# SparkFun_Blackberry_Trackballer_Breakout.net
KiCad netlist of a schematic drawn in EAGLE
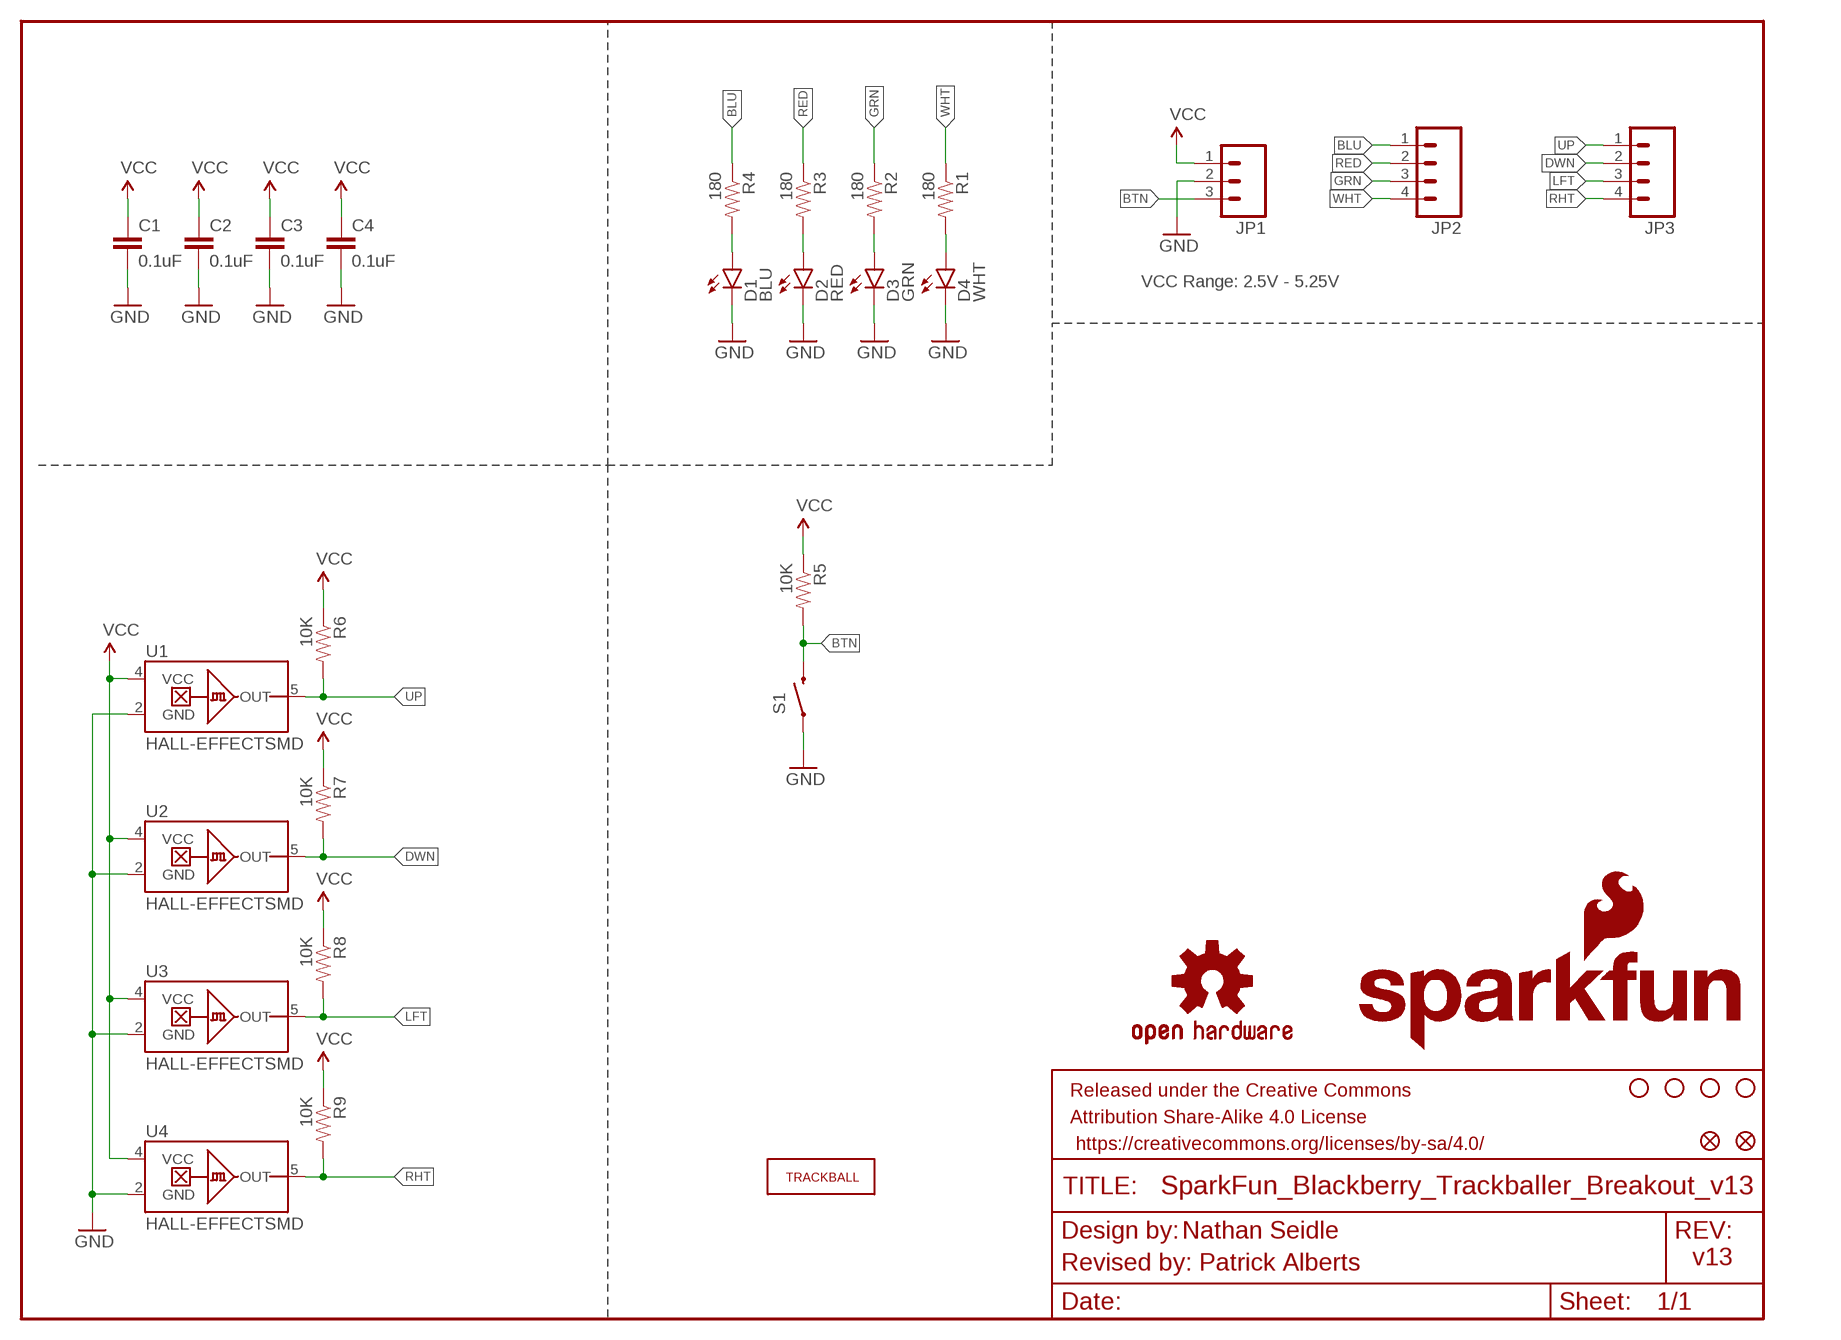
[diagram p0: schematic, sheet 1]

(export (version "E")
  (design (tool "Eeschema 10.0.6"))
  (components
    (comp (ref "C1")
      (value "0.1uF")
      (footprint "eagle-import:0603-CAP")
      (libsource (lib "eagle-import") (part "0.1UF-25V(+80/-20%)(0603)"))
    )
    (comp (ref "C2")
      (value "0.1uF")
      (footprint "eagle-import:0603-CAP")
      (libsource (lib "eagle-import") (part "0.1UF-25V(+80/-20%)(0603)"))
    )
    (comp (ref "C3")
      (value "0.1uF")
      (footprint "eagle-import:0603-CAP")
      (libsource (lib "eagle-import") (part "0.1UF-25V(+80/-20%)(0603)"))
    )
    (comp (ref "C4")
      (value "0.1uF")
      (footprint "eagle-import:0603-CAP")
      (libsource (lib "eagle-import") (part "0.1UF-25V(+80/-20%)(0603)"))
    )
    (comp (ref "D1")
      (value "BLU")
      (footprint "eagle-import:LED-0603")
      (libsource (lib "eagle-import") (part "LED-BLUE0603"))
    )
    (comp (ref "D2")
      (value "RED")
      (footprint "eagle-import:LED-0603")
      (libsource (lib "eagle-import") (part "LED-RED0603"))
    )
    (comp (ref "D3")
      (value "GRN")
      (footprint "eagle-import:LED-0603")
      (libsource (lib "eagle-import") (part "LED-GREEN0603"))
    )
    (comp (ref "D4")
      (value "WHT")
      (footprint "eagle-import:LED-0603")
      (libsource (lib "eagle-import") (part "LED-WHITE0603"))
    )
    (comp (ref "E$1")
      (value "FIDUCIAL1X2")
      (footprint "eagle-import:FIDUCIAL-1X2")
      (libsource (lib "eagle-import") (part "FIDUCIAL1X2"))
    )
    (comp (ref "E$2")
      (value "FIDUCIAL1X2")
      (footprint "eagle-import:FIDUCIAL-1X2")
      (libsource (lib "eagle-import") (part "FIDUCIAL1X2"))
    )
    (comp (ref "FRAME1")
      (value "FRAME-LETTER")
      (footprint "eagle-import:CREATIVE_COMMONS")
      (libsource (lib "eagle-import") (part "FRAME-LETTER"))
    )
    (comp (ref "JP1")
      (value "M03PTH")
      (footprint "eagle-import:1X03")
      (libsource (lib "eagle-import") (part "M03PTH"))
    )
    (comp (ref "JP2")
      (value "M04PTH")
      (footprint "eagle-import:1X04")
      (libsource (lib "eagle-import") (part "M04PTH"))
    )
    (comp (ref "JP3")
      (value "M04PTH")
      (footprint "eagle-import:1X04")
      (libsource (lib "eagle-import") (part "M04PTH"))
    )
    (comp (ref "LOGO1")
      (value "SFE_LOGO_NAME_FLAME.2_INCH")
      (footprint "eagle-import:SFE_LOGO_NAME_FLAME_.2")
      (libsource (lib "eagle-import") (part "SFE_LOGO_NAME_FLAME.2_INCH"))
    )
    (comp (ref "LOGO2")
      (value "OSHW-LOGOS")
      (footprint "eagle-import:OSHW-LOGO-S")
      (libsource (lib "eagle-import") (part "OSHW-LOGOS"))
    )
    (comp (ref "R1")
      (value "180")
      (footprint "eagle-import:0603-RES")
      (libsource (lib "eagle-import") (part "180OHM1/10W1%(0603)"))
    )
    (comp (ref "R2")
      (value "180")
      (footprint "eagle-import:0603-RES")
      (libsource (lib "eagle-import") (part "180OHM1/10W1%(0603)"))
    )
    (comp (ref "R3")
      (value "180")
      (footprint "eagle-import:0603-RES")
      (libsource (lib "eagle-import") (part "180OHM1/10W1%(0603)"))
    )
    (comp (ref "R4")
      (value "180")
      (footprint "eagle-import:0603-RES")
      (libsource (lib "eagle-import") (part "180OHM1/10W1%(0603)"))
    )
    (comp (ref "R5")
      (value "10K")
      (footprint "eagle-import:0603-RES")
      (libsource (lib "eagle-import") (part "10KOHM1/10W1%(0603)0603"))
    )
    (comp (ref "R6")
      (value "10K")
      (footprint "eagle-import:0603-RES")
      (libsource (lib "eagle-import") (part "10KOHM1/10W1%(0603)0603"))
    )
    (comp (ref "R7")
      (value "10K")
      (footprint "eagle-import:0603-RES")
      (libsource (lib "eagle-import") (part "10KOHM1/10W1%(0603)0603"))
    )
    (comp (ref "R8")
      (value "10K")
      (footprint "eagle-import:0603-RES")
      (libsource (lib "eagle-import") (part "10KOHM1/10W1%(0603)0603"))
    )
    (comp (ref "R9")
      (value "10K")
      (footprint "eagle-import:0603-RES")
      (libsource (lib "eagle-import") (part "10KOHM1/10W1%(0603)0603"))
    )
    (comp (ref "S1")
      (value "SWITCH-MOMENTARY-2SMD-2")
      (footprint "eagle-import:TACTILE_SWITCH_SMD-2")
      (libsource (lib "eagle-import") (part "SWITCH-MOMENTARY-2SMD-2"))
    )
    (comp (ref "U$1")
      (value "STAND-OFF")
      (footprint "eagle-import:STAND-OFF")
      (libsource (lib "eagle-import") (part "STAND-OFF"))
    )
    (comp (ref "U$3")
      (value "TRACKBALLMECH")
      (footprint "eagle-import:TRACKBALL")
      (libsource (lib "eagle-import") (part "TRACKBALLMECH"))
    )
    (comp (ref "U$8")
      (value "STAND-OFF")
      (footprint "eagle-import:STAND-OFF")
      (libsource (lib "eagle-import") (part "STAND-OFF"))
    )
    (comp (ref "U$11")
      (value "STAND-OFF")
      (footprint "eagle-import:STAND-OFF")
      (libsource (lib "eagle-import") (part "STAND-OFF"))
    )
    (comp (ref "U$14")
      (value "STAND-OFF")
      (footprint "eagle-import:STAND-OFF")
      (libsource (lib "eagle-import") (part "STAND-OFF"))
    )
    (comp (ref "U1")
      (value "HALL-EFFECTSMD")
      (footprint "eagle-import:SC70")
      (libsource (lib "eagle-import") (part "HALL-EFFECTSMD"))
    )
    (comp (ref "U2")
      (value "HALL-EFFECTSMD")
      (footprint "eagle-import:SC70")
      (libsource (lib "eagle-import") (part "HALL-EFFECTSMD"))
    )
    (comp (ref "U3")
      (value "HALL-EFFECTSMD")
      (footprint "eagle-import:SC70")
      (libsource (lib "eagle-import") (part "HALL-EFFECTSMD"))
    )
    (comp (ref "U4")
      (value "HALL-EFFECTSMD")
      (footprint "eagle-import:SC70")
      (libsource (lib "eagle-import") (part "HALL-EFFECTSMD"))
    )
  )
  (nets
    (net (code "1") (name "BLU") (class "Default")
      (node (ref "JP2") (pin "1") (pinfunction "1_1") (pintype "passive"))
      (node (ref "R4") (pin "1") (pinfunction "1_1") (pintype "passive"))
    )
    (net (code "2") (name "BTN") (class "Default")
      (node (ref "JP1") (pin "3") (pinfunction "3_3") (pintype "passive"))
      (node (ref "R5") (pin "2") (pinfunction "2_2") (pintype "passive"))
      (node (ref "S1") (pin "1") (pinfunction "2_1") (pintype "passive"))
    )
    (net (code "3") (name "DWN") (class "Default")
      (node (ref "JP3") (pin "2") (pinfunction "2_2") (pintype "passive"))
      (node (ref "R7") (pin "2") (pinfunction "2_2") (pintype "passive"))
      (node (ref "U2") (pin "5") (pinfunction "OUT_5") (pintype "bidirectional"))
    )
    (net (code "4") (name "GND") (class "Default")
      (node (ref "C1") (pin "2") (pinfunction "2_2") (pintype "passive"))
      (node (ref "C2") (pin "2") (pinfunction "2_2") (pintype "passive"))
      (node (ref "C3") (pin "2") (pinfunction "2_2") (pintype "passive"))
      (node (ref "C4") (pin "2") (pinfunction "2_2") (pintype "passive"))
      (node (ref "D1") (pin "C") (pinfunction "C_C") (pintype "passive"))
      (node (ref "D2") (pin "C") (pinfunction "C_C") (pintype "passive"))
      (node (ref "D3") (pin "C") (pinfunction "C_C") (pintype "passive"))
      (node (ref "D4") (pin "C") (pinfunction "C_C") (pintype "passive"))
      (node (ref "JP1") (pin "2") (pinfunction "2_2") (pintype "passive"))
      (node (ref "S1") (pin "2") (pinfunction "1_2") (pintype "passive"))
      (node (ref "U1") (pin "2") (pinfunction "GND_2") (pintype "bidirectional"))
      (node (ref "U2") (pin "2") (pinfunction "GND_2") (pintype "bidirectional"))
      (node (ref "U3") (pin "2") (pinfunction "GND_2") (pintype "bidirectional"))
      (node (ref "U4") (pin "2") (pinfunction "GND_2") (pintype "bidirectional"))
    )
    (net (code "5") (name "GRN") (class "Default")
      (node (ref "JP2") (pin "3") (pinfunction "3_3") (pintype "passive"))
      (node (ref "R2") (pin "1") (pinfunction "1_1") (pintype "passive"))
    )
    (net (code "6") (name "LFT") (class "Default")
      (node (ref "JP3") (pin "3") (pinfunction "3_3") (pintype "passive"))
      (node (ref "R8") (pin "2") (pinfunction "2_2") (pintype "passive"))
      (node (ref "U3") (pin "5") (pinfunction "OUT_5") (pintype "bidirectional"))
    )
    (net (code "7") (name "Net-(D1-PadA)") (class "Default")
      (node (ref "D1") (pin "A") (pinfunction "A_A") (pintype "passive"))
      (node (ref "R4") (pin "2") (pinfunction "2_2") (pintype "passive"))
    )
    (net (code "8") (name "Net-(D2-PadA)") (class "Default")
      (node (ref "D2") (pin "A") (pinfunction "A_A") (pintype "passive"))
      (node (ref "R3") (pin "2") (pinfunction "2_2") (pintype "passive"))
    )
    (net (code "9") (name "Net-(D3-PadA)") (class "Default")
      (node (ref "D3") (pin "A") (pinfunction "A_A") (pintype "passive"))
      (node (ref "R2") (pin "2") (pinfunction "2_2") (pintype "passive"))
    )
    (net (code "10") (name "Net-(D4-PadA)") (class "Default")
      (node (ref "D4") (pin "A") (pinfunction "A_A") (pintype "passive"))
      (node (ref "R1") (pin "2") (pinfunction "2_2") (pintype "passive"))
    )
    (net (code "11") (name "RED") (class "Default")
      (node (ref "JP2") (pin "2") (pinfunction "2_2") (pintype "passive"))
      (node (ref "R3") (pin "1") (pinfunction "1_1") (pintype "passive"))
    )
    (net (code "12") (name "RHT") (class "Default")
      (node (ref "JP3") (pin "4") (pinfunction "4_4") (pintype "passive"))
      (node (ref "R9") (pin "2") (pinfunction "2_2") (pintype "passive"))
      (node (ref "U4") (pin "5") (pinfunction "OUT_5") (pintype "bidirectional"))
    )
    (net (code "13") (name "UP") (class "Default")
      (node (ref "JP3") (pin "1") (pinfunction "1_1") (pintype "passive"))
      (node (ref "R6") (pin "2") (pinfunction "2_2") (pintype "passive"))
      (node (ref "U1") (pin "5") (pinfunction "OUT_5") (pintype "bidirectional"))
    )
    (net (code "14") (name "VCC") (class "Default")
      (node (ref "C1") (pin "1") (pinfunction "1_1") (pintype "passive"))
      (node (ref "C2") (pin "1") (pinfunction "1_1") (pintype "passive"))
      (node (ref "C3") (pin "1") (pinfunction "1_1") (pintype "passive"))
      (node (ref "C4") (pin "1") (pinfunction "1_1") (pintype "passive"))
      (node (ref "JP1") (pin "1") (pinfunction "1_1") (pintype "passive"))
      (node (ref "R5") (pin "1") (pinfunction "1_1") (pintype "passive"))
      (node (ref "R6") (pin "1") (pinfunction "1_1") (pintype "passive"))
      (node (ref "R7") (pin "1") (pinfunction "1_1") (pintype "passive"))
      (node (ref "R8") (pin "1") (pinfunction "1_1") (pintype "passive"))
      (node (ref "R9") (pin "1") (pinfunction "1_1") (pintype "passive"))
      (node (ref "U1") (pin "4") (pinfunction "VCC_4") (pintype "bidirectional"))
      (node (ref "U2") (pin "4") (pinfunction "VCC_4") (pintype "bidirectional"))
      (node (ref "U3") (pin "4") (pinfunction "VCC_4") (pintype "bidirectional"))
      (node (ref "U4") (pin "4") (pinfunction "VCC_4") (pintype "bidirectional"))
    )
    (net (code "15") (name "WHT") (class "Default")
      (node (ref "JP2") (pin "4") (pinfunction "4_4") (pintype "passive"))
      (node (ref "R1") (pin "1") (pinfunction "1_1") (pintype "passive"))
    )
  )
)
